# Test_Sled_Pad_Valves_Schematic_EasyEDA.net
KiCad netlist of a schematic drawn in EasyEDA
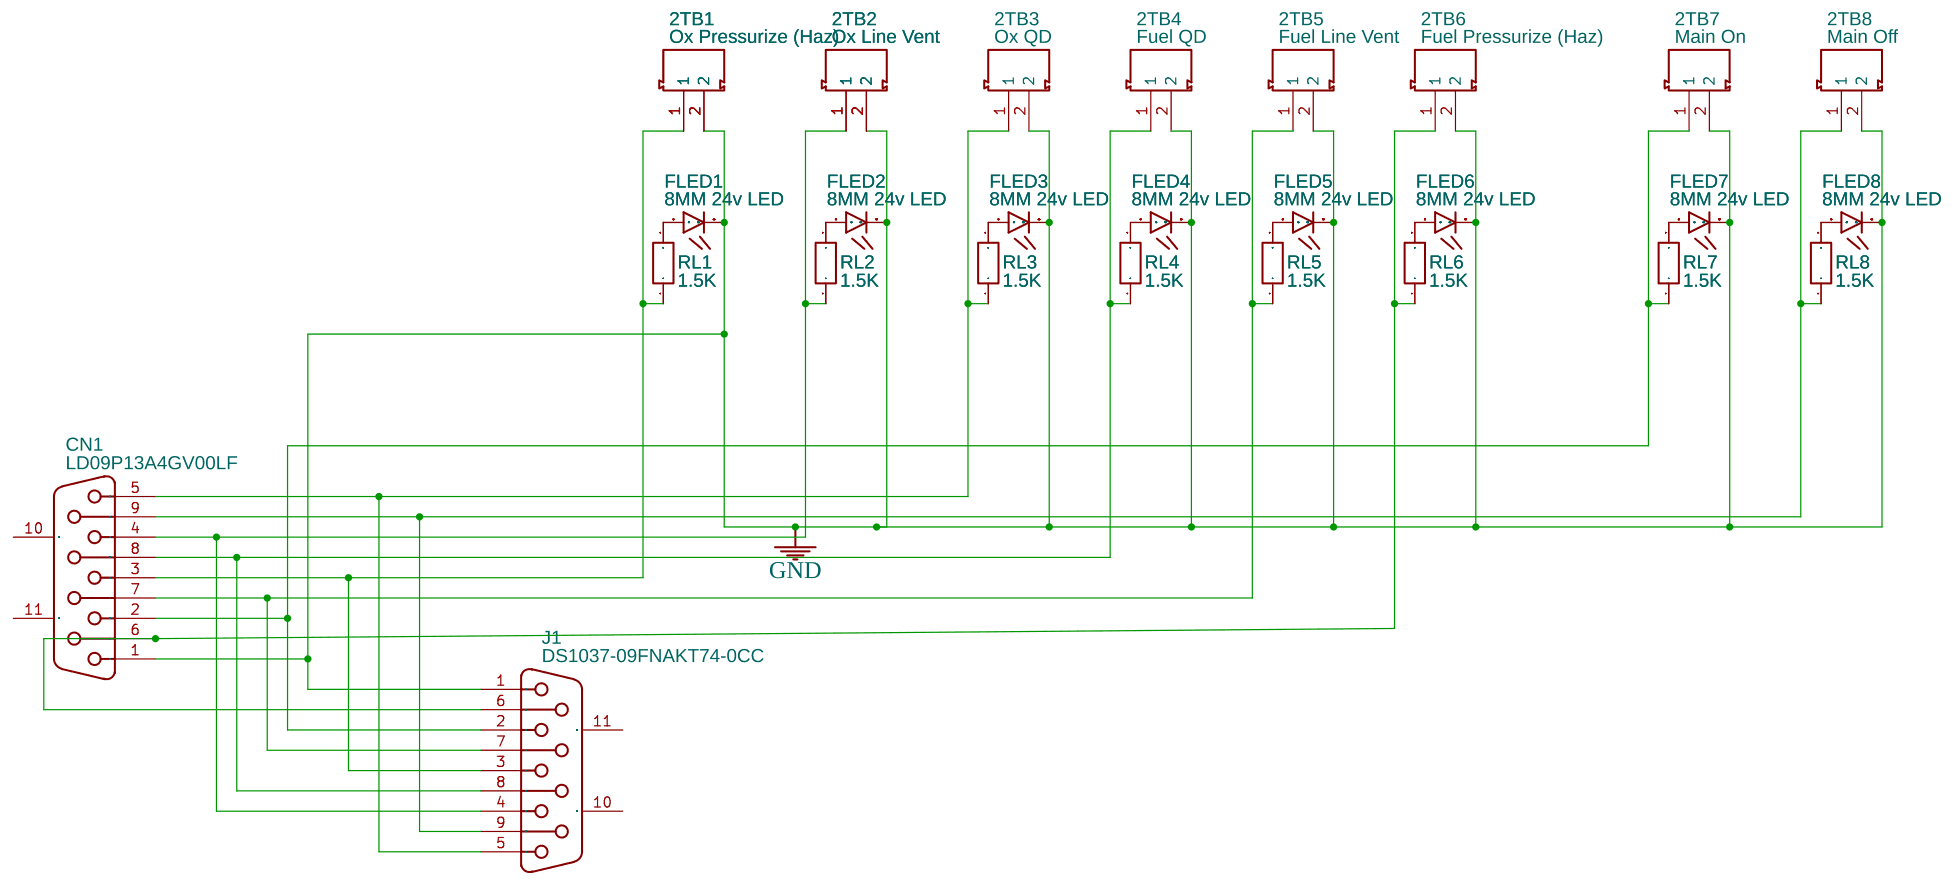
[diagram p0: schematic sheet]

(export (version "E")
  (design (tool "Eeschema 10.0.6"))
  (components
    (comp (ref "2TB1")
      (value "Ox Pressurize (Haz)")
      (fields (field (name "Manufacturer Part") "1729128") (field (name "Manufacturer") "Phoenix Contact"))
      (libsource (lib "") (part "1729128"))
    )
    (comp (ref "2TB2")
      (value "Ox Line Vent")
      (fields (field (name "Manufacturer Part") "1729128") (field (name "Manufacturer") "Phoenix Contact"))
      (libsource (lib "") (part "1729128"))
    )
    (comp (ref "2TB3")
      (value "Ox QD")
      (fields (field (name "Manufacturer Part") "1729128") (field (name "Manufacturer") "Phoenix Contact"))
      (libsource (lib "") (part "1729128"))
    )
    (comp (ref "2TB4")
      (value "Fuel QD")
      (fields (field (name "Manufacturer Part") "1729128") (field (name "Manufacturer") "Phoenix Contact"))
      (libsource (lib "") (part "1729128"))
    )
    (comp (ref "2TB5")
      (value "Fuel Line Vent")
      (fields (field (name "Manufacturer Part") "1729128") (field (name "Manufacturer") "Phoenix Contact"))
      (libsource (lib "") (part "1729128"))
    )
    (comp (ref "2TB6")
      (value "Fuel Pressurize (Haz)")
      (fields (field (name "Manufacturer Part") "1729128") (field (name "Manufacturer") "Phoenix Contact"))
      (libsource (lib "") (part "1729128"))
    )
    (comp (ref "2TB7")
      (value "Main On")
      (fields (field (name "Manufacturer Part") "1729128") (field (name "Manufacturer") "Phoenix Contact"))
      (libsource (lib "") (part "1729128"))
    )
    (comp (ref "2TB8")
      (value "Main Off")
      (fields (field (name "Manufacturer Part") "1729128") (field (name "Manufacturer") "Phoenix Contact"))
      (libsource (lib "") (part "1729128"))
    )
    (comp (ref "CN1")
      (value "LD09P13A4GV00LF")
      (fields (field (name "Manufacturer") "Amphenol"))
      (libsource (lib "") (part "LD09P13A4GV00LF"))
    )
    (comp (ref "FLED1") (value "8MM 24v LED") (libsource (lib "") (part "P804JPF4D")))
    (comp (ref "FLED2") (value "8MM 24v LED") (libsource (lib "") (part "P804JPF4D")))
    (comp (ref "FLED3") (value "8MM 24v LED") (libsource (lib "") (part "P804JPF4D")))
    (comp (ref "FLED4") (value "8MM 24v LED") (libsource (lib "") (part "P804JPF4D")))
    (comp (ref "FLED5") (value "8MM 24v LED") (libsource (lib "") (part "P804JPF4D")))
    (comp (ref "FLED6") (value "8MM 24v LED") (libsource (lib "") (part "P804JPF4D")))
    (comp (ref "FLED7") (value "8MM 24v LED") (libsource (lib "") (part "P804JPF4D")))
    (comp (ref "FLED8") (value "8MM 24v LED") (libsource (lib "") (part "P804JPF4D")))
    (comp (ref "J1")
      (value "DS1037-09FNAKT74-0CC")
      (fields (field (name "Manufacturer") "CONNFLY"))
      (libsource (lib "") (part "DS1037-09FNAKT74-0CC"))
    )
    (comp (ref "RL1")
      (value "1.5K")
      (fields (field (name "Manufacturer Part") "SFR03EZPF1001") (field (name "Manufacturer") "ROHM(罗姆)"))
      (libsource (lib "") (part "SFR03EZPF1001"))
    )
    (comp (ref "RL2")
      (value "1.5K")
      (fields (field (name "Manufacturer Part") "SFR03EZPF1001") (field (name "Manufacturer") "ROHM(罗姆)"))
      (libsource (lib "") (part "SFR03EZPF1001"))
    )
    (comp (ref "RL3")
      (value "1.5K")
      (fields (field (name "Manufacturer Part") "SFR03EZPF1001") (field (name "Manufacturer") "ROHM(罗姆)"))
      (libsource (lib "") (part "SFR03EZPF1001"))
    )
    (comp (ref "RL4")
      (value "1.5K")
      (fields (field (name "Manufacturer Part") "SFR03EZPF1001") (field (name "Manufacturer") "ROHM(罗姆)"))
      (libsource (lib "") (part "SFR03EZPF1001"))
    )
    (comp (ref "RL5")
      (value "1.5K")
      (fields (field (name "Manufacturer Part") "SFR03EZPF1001") (field (name "Manufacturer") "ROHM(罗姆)"))
      (libsource (lib "") (part "SFR03EZPF1001"))
    )
    (comp (ref "RL6")
      (value "1.5K")
      (fields (field (name "Manufacturer Part") "SFR03EZPF1001") (field (name "Manufacturer") "ROHM(罗姆)"))
      (libsource (lib "") (part "SFR03EZPF1001"))
    )
    (comp (ref "RL7")
      (value "1.5K")
      (fields (field (name "Manufacturer Part") "SFR03EZPF1001") (field (name "Manufacturer") "ROHM(罗姆)"))
      (libsource (lib "") (part "SFR03EZPF1001"))
    )
    (comp (ref "RL8")
      (value "1.5K")
      (fields (field (name "Manufacturer Part") "SFR03EZPF1001") (field (name "Manufacturer") "ROHM(罗姆)"))
      (libsource (lib "") (part "SFR03EZPF1001"))
    )
  )
  (nets
    (net (code "1") (name "GND") (class "Default")
      (node (ref "2TB1") (pin "2") (pinfunction "2_2") (pintype "unspecified"))
      (node (ref "2TB2") (pin "2") (pinfunction "2_2") (pintype "unspecified"))
      (node (ref "2TB3") (pin "2") (pinfunction "2_2") (pintype "unspecified"))
      (node (ref "2TB4") (pin "2") (pinfunction "2_2") (pintype "unspecified"))
      (node (ref "2TB5") (pin "2") (pinfunction "2_2") (pintype "unspecified"))
      (node (ref "2TB6") (pin "2") (pinfunction "2_2") (pintype "unspecified"))
      (node (ref "2TB7") (pin "2") (pinfunction "2_2") (pintype "unspecified"))
      (node (ref "2TB8") (pin "2") (pinfunction "2_2") (pintype "unspecified"))
      (node (ref "CN1") (pin "1") (pinfunction "1_1") (pintype "input"))
      (node (ref "FLED1") (pin "CATHODE") (pinfunction "CATHODE_CATHODE") (pintype "unspecified"))
      (node (ref "FLED2") (pin "CATHODE") (pinfunction "CATHODE_CATHODE") (pintype "unspecified"))
      (node (ref "FLED3") (pin "CATHODE") (pinfunction "CATHODE_CATHODE") (pintype "unspecified"))
      (node (ref "FLED4") (pin "CATHODE") (pinfunction "CATHODE_CATHODE") (pintype "unspecified"))
      (node (ref "FLED5") (pin "CATHODE") (pinfunction "CATHODE_CATHODE") (pintype "unspecified"))
      (node (ref "FLED6") (pin "CATHODE") (pinfunction "CATHODE_CATHODE") (pintype "unspecified"))
      (node (ref "FLED7") (pin "CATHODE") (pinfunction "CATHODE_CATHODE") (pintype "unspecified"))
      (node (ref "FLED8") (pin "CATHODE") (pinfunction "CATHODE_CATHODE") (pintype "unspecified"))
      (node (ref "J1") (pin "1") (pinfunction "1_1") (pintype "input"))
    )
    (net (code "2") (name "Net-(2TB1-Pad1)") (class "Default")
      (node (ref "2TB1") (pin "1") (pinfunction "1_1") (pintype "unspecified"))
      (node (ref "CN1") (pin "3") (pinfunction "3_3") (pintype "input"))
      (node (ref "J1") (pin "3") (pinfunction "3_3") (pintype "input"))
      (node (ref "RL1") (pin "1") (pinfunction "1_1") (pintype "unspecified"))
    )
    (net (code "3") (name "Net-(2TB2-Pad1)") (class "Default")
      (node (ref "2TB2") (pin "1") (pinfunction "1_1") (pintype "unspecified"))
      (node (ref "CN1") (pin "4") (pinfunction "4_4") (pintype "input"))
      (node (ref "J1") (pin "4") (pinfunction "4_4") (pintype "input"))
      (node (ref "RL2") (pin "1") (pinfunction "1_1") (pintype "unspecified"))
    )
    (net (code "4") (name "Net-(2TB3-Pad1)") (class "Default")
      (node (ref "2TB3") (pin "1") (pinfunction "1_1") (pintype "unspecified"))
      (node (ref "CN1") (pin "5") (pinfunction "5_5") (pintype "input"))
      (node (ref "J1") (pin "5") (pinfunction "5_5") (pintype "input"))
      (node (ref "RL3") (pin "1") (pinfunction "1_1") (pintype "unspecified"))
    )
    (net (code "5") (name "Net-(2TB4-Pad1)") (class "Default")
      (node (ref "2TB4") (pin "1") (pinfunction "1_1") (pintype "unspecified"))
      (node (ref "CN1") (pin "8") (pinfunction "8_8") (pintype "input"))
      (node (ref "J1") (pin "8") (pinfunction "8_8") (pintype "input"))
      (node (ref "RL4") (pin "1") (pinfunction "1_1") (pintype "unspecified"))
    )
    (net (code "6") (name "Net-(2TB5-Pad1)") (class "Default")
      (node (ref "2TB5") (pin "1") (pinfunction "1_1") (pintype "unspecified"))
      (node (ref "CN1") (pin "7") (pinfunction "7_7") (pintype "input"))
      (node (ref "J1") (pin "7") (pinfunction "7_7") (pintype "input"))
      (node (ref "RL5") (pin "1") (pinfunction "1_1") (pintype "unspecified"))
    )
    (net (code "7") (name "Net-(2TB6-Pad1)") (class "Default")
      (node (ref "2TB6") (pin "1") (pinfunction "1_1") (pintype "unspecified"))
      (node (ref "CN1") (pin "6") (pinfunction "6_6") (pintype "input"))
      (node (ref "J1") (pin "6") (pinfunction "6_6") (pintype "input"))
      (node (ref "RL6") (pin "1") (pinfunction "1_1") (pintype "unspecified"))
    )
    (net (code "8") (name "Net-(2TB7-Pad1)") (class "Default")
      (node (ref "2TB7") (pin "1") (pinfunction "1_1") (pintype "unspecified"))
      (node (ref "CN1") (pin "2") (pinfunction "2_2") (pintype "input"))
      (node (ref "J1") (pin "2") (pinfunction "2_2") (pintype "input"))
      (node (ref "RL7") (pin "1") (pinfunction "1_1") (pintype "unspecified"))
    )
    (net (code "9") (name "Net-(2TB8-Pad1)") (class "Default")
      (node (ref "2TB8") (pin "1") (pinfunction "1_1") (pintype "unspecified"))
      (node (ref "CN1") (pin "9") (pinfunction "9_9") (pintype "input"))
      (node (ref "J1") (pin "9") (pinfunction "9_9") (pintype "input"))
      (node (ref "RL8") (pin "1") (pinfunction "1_1") (pintype "unspecified"))
    )
    (net (code "10") (name "Net-(FLED1-PadANODE)") (class "Default")
      (node (ref "FLED1") (pin "ANODE") (pinfunction "ANODE_ANODE") (pintype "unspecified"))
      (node (ref "RL1") (pin "2") (pinfunction "2_2") (pintype "unspecified"))
    )
    (net (code "11") (name "Net-(FLED2-PadANODE)") (class "Default")
      (node (ref "FLED2") (pin "ANODE") (pinfunction "ANODE_ANODE") (pintype "unspecified"))
      (node (ref "RL2") (pin "2") (pinfunction "2_2") (pintype "unspecified"))
    )
    (net (code "12") (name "Net-(FLED3-PadANODE)") (class "Default")
      (node (ref "FLED3") (pin "ANODE") (pinfunction "ANODE_ANODE") (pintype "unspecified"))
      (node (ref "RL3") (pin "2") (pinfunction "2_2") (pintype "unspecified"))
    )
    (net (code "13") (name "Net-(FLED4-PadANODE)") (class "Default")
      (node (ref "FLED4") (pin "ANODE") (pinfunction "ANODE_ANODE") (pintype "unspecified"))
      (node (ref "RL4") (pin "2") (pinfunction "2_2") (pintype "unspecified"))
    )
    (net (code "14") (name "Net-(FLED5-PadANODE)") (class "Default")
      (node (ref "FLED5") (pin "ANODE") (pinfunction "ANODE_ANODE") (pintype "unspecified"))
      (node (ref "RL5") (pin "2") (pinfunction "2_2") (pintype "unspecified"))
    )
    (net (code "15") (name "Net-(FLED6-PadANODE)") (class "Default")
      (node (ref "FLED6") (pin "ANODE") (pinfunction "ANODE_ANODE") (pintype "unspecified"))
      (node (ref "RL6") (pin "2") (pinfunction "2_2") (pintype "unspecified"))
    )
    (net (code "16") (name "Net-(FLED7-PadANODE)") (class "Default")
      (node (ref "FLED7") (pin "ANODE") (pinfunction "ANODE_ANODE") (pintype "unspecified"))
      (node (ref "RL7") (pin "2") (pinfunction "2_2") (pintype "unspecified"))
    )
    (net (code "17") (name "Net-(FLED8-PadANODE)") (class "Default")
      (node (ref "FLED8") (pin "ANODE") (pinfunction "ANODE_ANODE") (pintype "unspecified"))
      (node (ref "RL8") (pin "2") (pinfunction "2_2") (pintype "unspecified"))
    )
    (net (code "18") (name "unconnected-(CN1-MH1-Pad10)") (class "Default")
      (node (ref "CN1") (pin "10") (pinfunction "MH1_10") (pintype "input"))
    )
    (net (code "19") (name "unconnected-(CN1-MH2-Pad11)") (class "Default")
      (node (ref "CN1") (pin "11") (pinfunction "MH2_11") (pintype "input"))
    )
    (net (code "20") (name "unconnected-(J1-MH1-Pad10)") (class "Default")
      (node (ref "J1") (pin "10") (pinfunction "MH1_10") (pintype "input"))
    )
    (net (code "21") (name "unconnected-(J1-MH2-Pad11)") (class "Default")
      (node (ref "J1") (pin "11") (pinfunction "MH2_11") (pintype "input"))
    )
  )
)
